# SCH_Mesa_Endstops_2022-06-12.net
KiCad netlist of a schematic drawn in EasyEDA
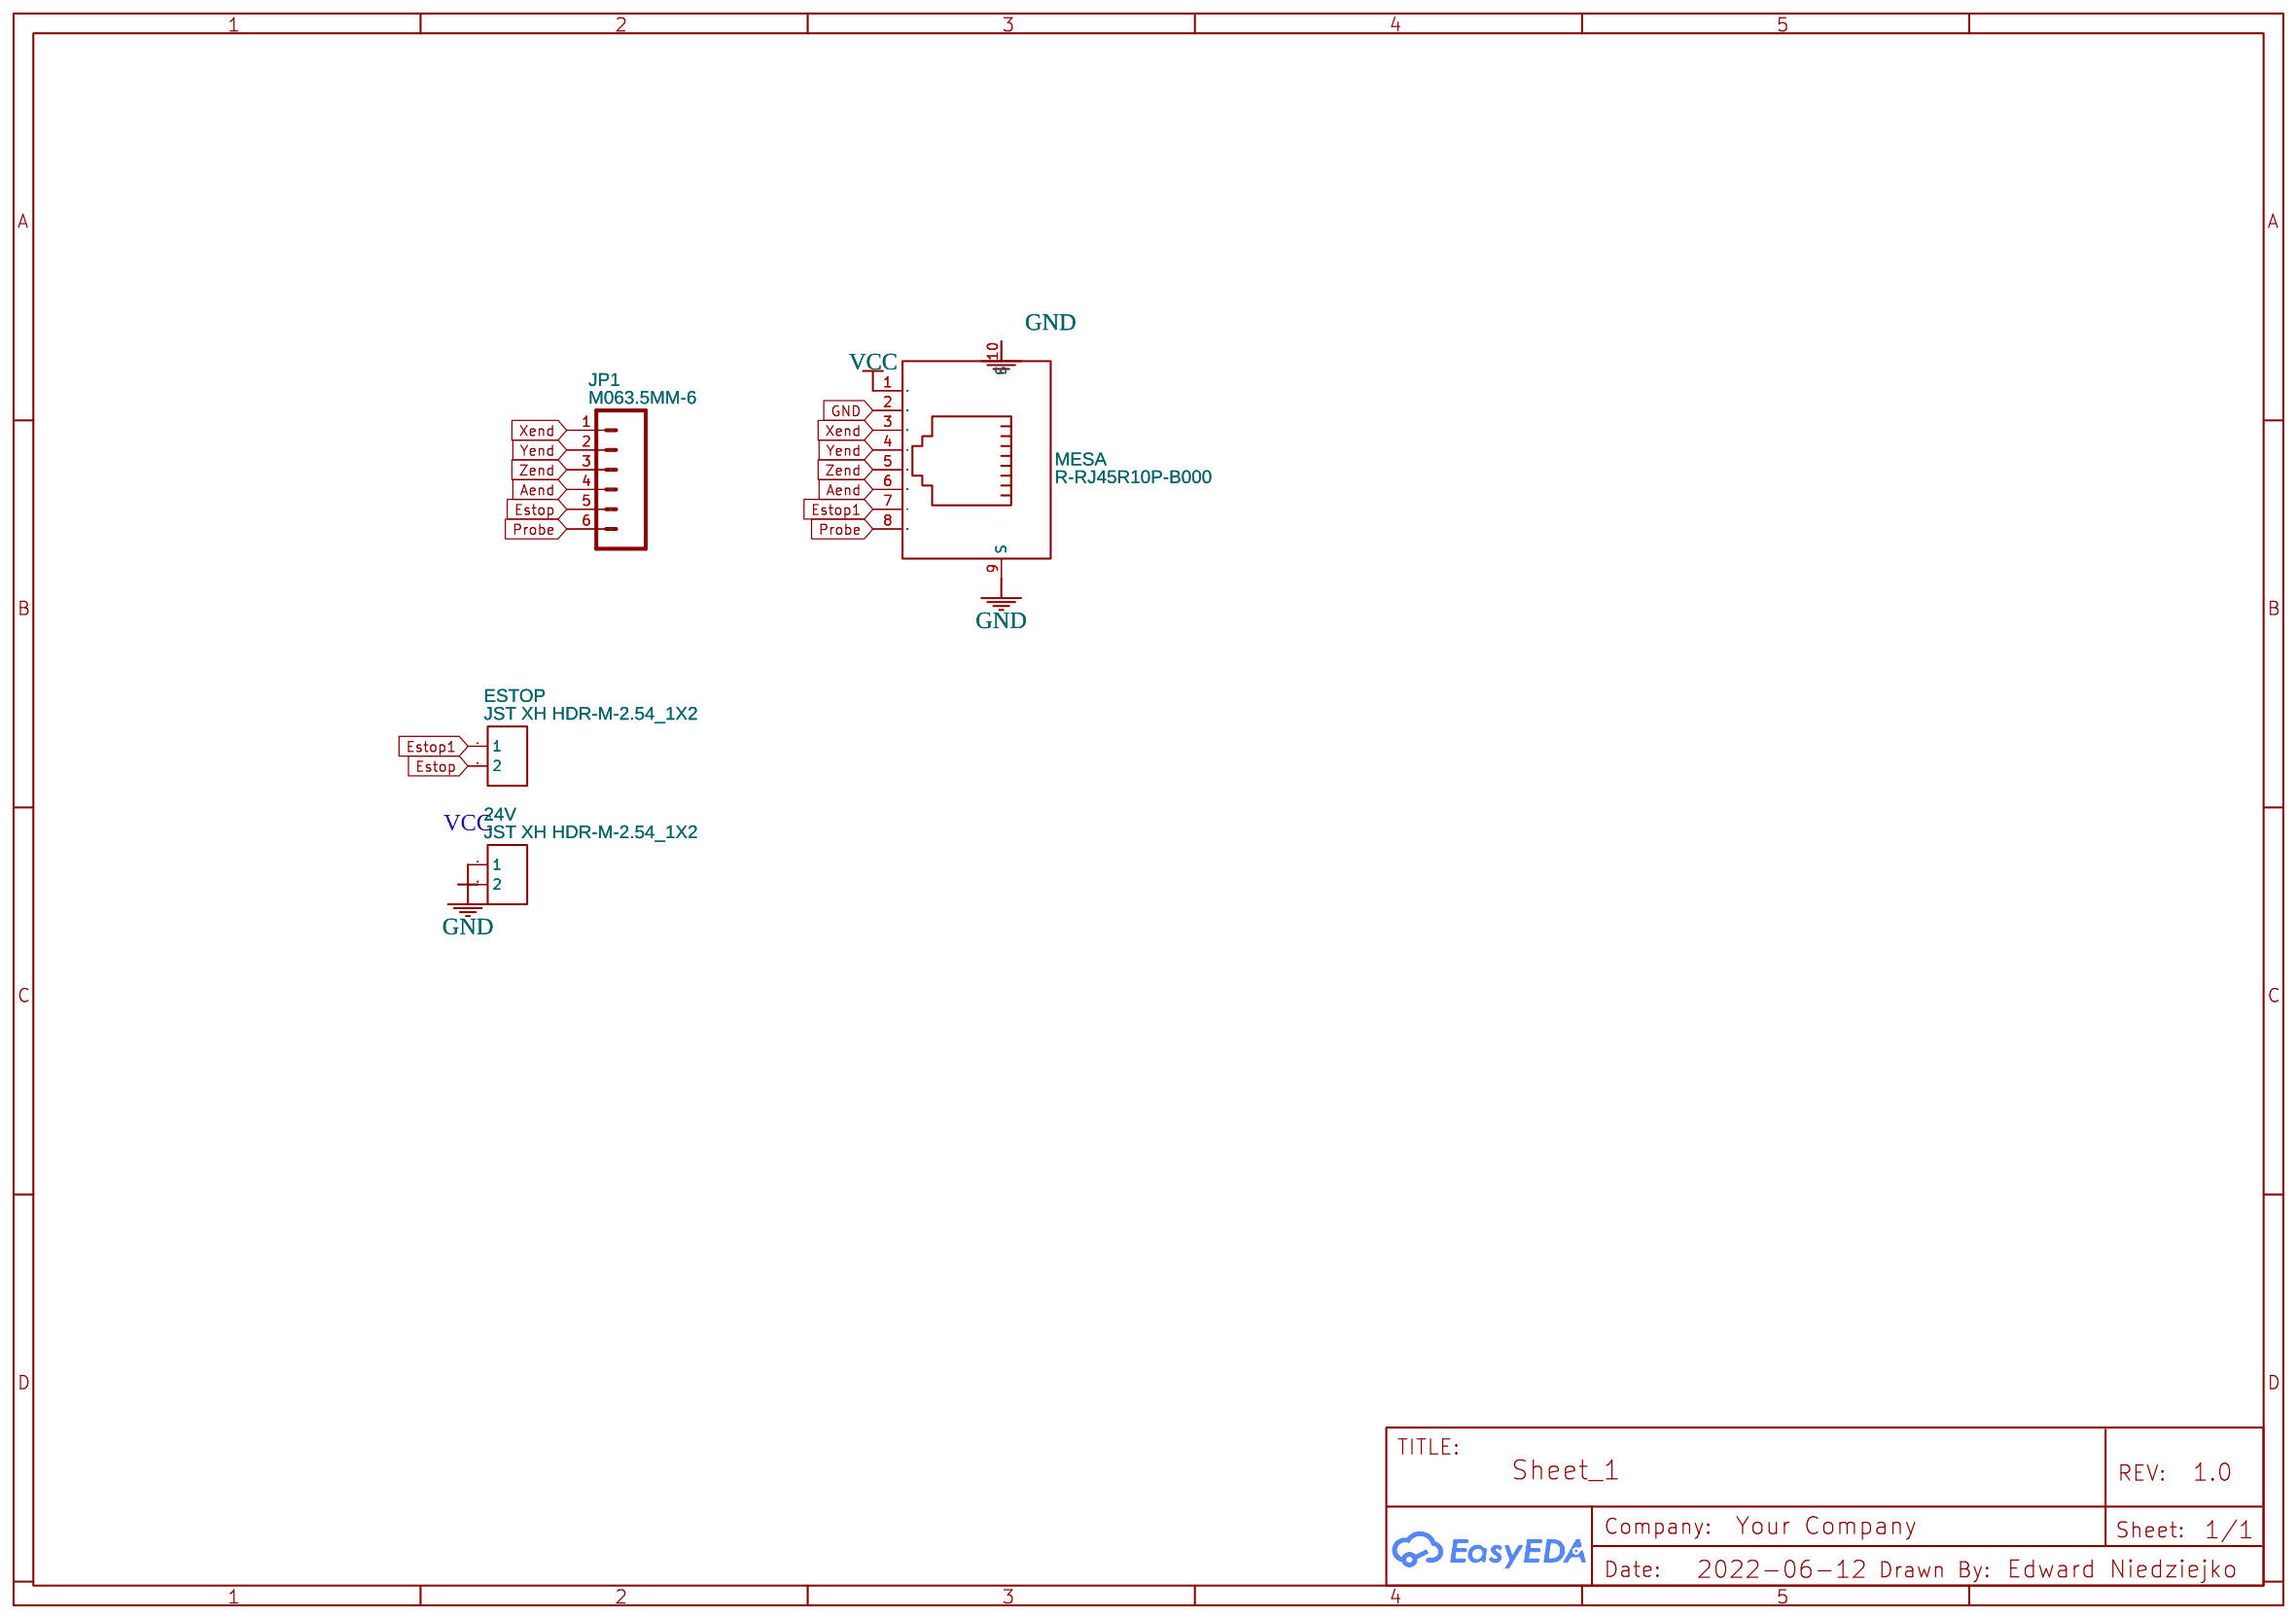
[diagram p0: schematic sheet]

(export (version "E")
  (design (tool "Eeschema 10.0.6"))
  (components
    (comp (ref "24V")
      (value "JST XH HDR-M-2.54_1X2")
      (fields (field (name "BOM_Supplier Part") "C49661"))
      (libsource (lib "") (part "JST XH HDR-M-2.54_1X2_1"))
    )
    (comp (ref "ESTOP")
      (value "JST XH HDR-M-2.54_1X2")
      (fields (field (name "BOM_Supplier Part") "C49661"))
      (libsource (lib "") (part "JST XH HDR-M-2.54_1X2"))
    )
    (comp (ref "JP1") (value "M063.5MM-6") (libsource (lib "") (part "M063.5MM-6")))
    (comp (ref "MESA")
      (value "R-RJ45R10P-B000")
      (fields (field (name "BOM_Supplier Part") "C386758"))
      (libsource (lib "") (part "R-RJ45R10P-B000"))
    )
  )
  (nets
    (net (code "1") (name "Aend") (class "Default")
      (node (ref "JP1") (pin "4") (pinfunction "4_4") (pintype "unspecified"))
      (node (ref "MESA") (pin "6") (pinfunction "6_6") (pintype "unspecified"))
    )
    (net (code "2") (name "Estop") (class "Default")
      (node (ref "ESTOP") (pin "2") (pinfunction "2_2") (pintype "input"))
      (node (ref "JP1") (pin "5") (pinfunction "5_5") (pintype "unspecified"))
    )
    (net (code "3") (name "Estop1") (class "Default")
      (node (ref "ESTOP") (pin "1") (pinfunction "1_1") (pintype "input"))
      (node (ref "MESA") (pin "7") (pinfunction "7_7") (pintype "unspecified"))
    )
    (net (code "4") (name "GND") (class "Default")
      (node (ref "24V") (pin "2") (pinfunction "2_2") (pintype "input"))
      (node (ref "MESA") (pin "10") (pinfunction "S_10") (pintype "unspecified"))
      (node (ref "MESA") (pin "2") (pinfunction "2_2") (pintype "unspecified"))
      (node (ref "MESA") (pin "9") (pinfunction "S_9") (pintype "unspecified"))
    )
    (net (code "5") (name "Probe") (class "Default")
      (node (ref "JP1") (pin "6") (pinfunction "6_6") (pintype "unspecified"))
      (node (ref "MESA") (pin "8") (pinfunction "8_8") (pintype "unspecified"))
    )
    (net (code "6") (name "VCC") (class "Default")
      (node (ref "24V") (pin "1") (pinfunction "1_1") (pintype "input"))
      (node (ref "MESA") (pin "1") (pinfunction "1_1") (pintype "unspecified"))
    )
    (net (code "7") (name "Xend") (class "Default")
      (node (ref "JP1") (pin "1") (pinfunction "1_1") (pintype "unspecified"))
      (node (ref "MESA") (pin "3") (pinfunction "3_3") (pintype "unspecified"))
    )
    (net (code "8") (name "Yend") (class "Default")
      (node (ref "JP1") (pin "2") (pinfunction "2_2") (pintype "unspecified"))
      (node (ref "MESA") (pin "4") (pinfunction "4_4") (pintype "unspecified"))
    )
    (net (code "9") (name "Zend") (class "Default")
      (node (ref "JP1") (pin "3") (pinfunction "3_3") (pintype "unspecified"))
      (node (ref "MESA") (pin "5") (pinfunction "5_5") (pintype "unspecified"))
    )
  )
)
